# artPancreas.net
KiCad netlist of a schematic drawn in EAGLE
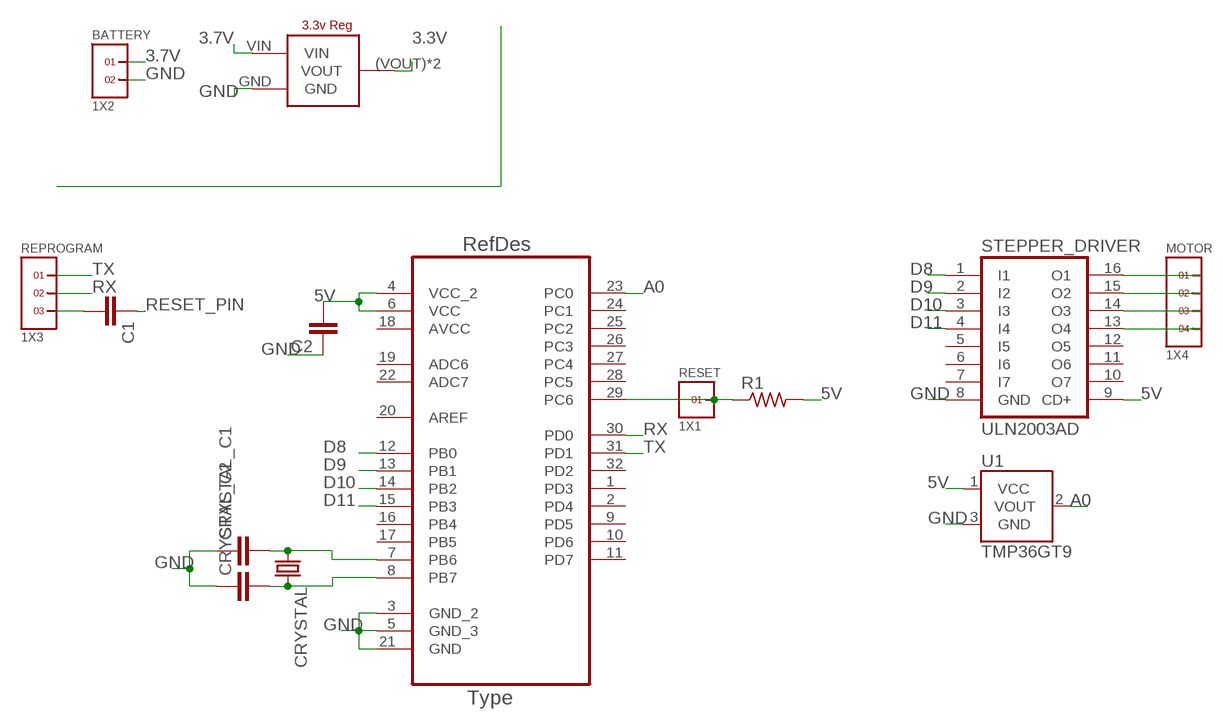
[diagram p0: schematic, sheet 1]

(export (version "E")
  (design (tool "Eeschema 10.0.6"))
  (components
    (comp (ref "ATMEGA328SMD")
      (value "ATMEGA328P-AU")
      (footprint "eagle-import:QFP80P900X900X120-32N")
      (libsource (lib "eagle-import") (part "ATMEGA328P-AU"))
    )
    (comp (ref "BATTERY")
      (value "1X2")
      (footprint "eagle-import:1X2")
      (libsource (lib "eagle-import") (part "1X2"))
    )
    (comp (ref "C1")
      (value "C2,5-3")
      (footprint "eagle-import:C2.5-3")
      (libsource (lib "eagle-import") (part "C2,5-3"))
    )
    (comp (ref "C2")
      (value "C2,5-3")
      (footprint "eagle-import:C2.5-3")
      (libsource (lib "eagle-import") (part "C2,5-3"))
    )
    (comp (ref "CRYSTAL")
      (value "CRYSTALHC18U-V")
      (footprint "eagle-import:HC18U-V")
      (libsource (lib "eagle-import") (part "CRYSTALHC18U-V"))
    )
    (comp (ref "CRYSTAL_C1")
      (value "C2,5-3")
      (footprint "eagle-import:C2.5-3")
      (libsource (lib "eagle-import") (part "C2,5-3"))
    )
    (comp (ref "CRYSTAL_C2")
      (value "C2,5-3")
      (footprint "eagle-import:C2.5-3")
      (libsource (lib "eagle-import") (part "C2,5-3"))
    )
    (comp (ref "MOTOR")
      (value "1X4")
      (footprint "eagle-import:1X4")
      (libsource (lib "eagle-import") (part "1X4"))
    )
    (comp (ref "R1")
      (value "R-US_0204/5")
      (footprint "eagle-import:0204_5")
      (libsource (lib "eagle-import") (part "R-US_0204/5"))
    )
    (comp (ref "REPROGRAM")
      (value "1X3")
      (footprint "eagle-import:1X3")
      (libsource (lib "eagle-import") (part "1X3"))
    )
    (comp (ref "RESET")
      (value "1X1")
      (footprint "eagle-import:1X1")
      (libsource (lib "eagle-import") (part "1X1"))
    )
    (comp (ref "STEPPER_DRIVER")
      (value "ULN2003AD")
      (footprint "eagle-import:SO16")
      (libsource (lib "eagle-import") (part "ULN2003AD"))
    )
    (comp (ref "U$1")
      (value "LD1117")
      (footprint "eagle-import:LD1117SOT-223")
      (libsource (lib "eagle-import") (part "LD1117"))
    )
    (comp (ref "U1")
      (value "TMP36GT9")
      (footprint "eagle-import:TO-92")
      (fields (field (name "MF") "Analog Devices") (field (name "MP") "TMP36"))
      (libsource (lib "eagle-import") (part "TMP36GT9"))
    )
  )
  (nets
    (net (code "1") (name "/3.3V") (class "Default")
      (node (ref "U$1") (pin "(VOUT)") (pinfunction "VOUT_(VOUT)") (pintype "bidirectional"))
      (node (ref "U$1") (pin "VOUT") (pinfunction "VOUT_VOUT") (pintype "bidirectional"))
    )
    (net (code "2") (name "/3.7V") (class "Default")
      (node (ref "BATTERY") (pin "1") (pinfunction "1_1") (pintype "bidirectional"))
      (node (ref "U$1") (pin "VIN") (pinfunction "VIN_VIN") (pintype "bidirectional"))
    )
    (net (code "3") (name "/5V") (class "Default")
      (node (ref "ATMEGA328SMD") (pin "4") (pinfunction "VCC_2_4") (pintype "power_in"))
      (node (ref "ATMEGA328SMD") (pin "6") (pinfunction "VCC_6") (pintype "power_in"))
      (node (ref "C2") (pin "2") (pinfunction "2_2") (pintype "passive"))
      (node (ref "R1") (pin "2") (pinfunction "2_2") (pintype "passive"))
      (node (ref "STEPPER_DRIVER") (pin "9") (pinfunction "CD+_9") (pintype "passive"))
      (node (ref "U1") (pin "1") (pinfunction "VCC_1") (pintype "bidirectional"))
    )
    (net (code "4") (name "/A0") (class "Default")
      (node (ref "ATMEGA328SMD") (pin "23") (pinfunction "PC0_23") (pintype "bidirectional"))
      (node (ref "U1") (pin "2") (pinfunction "VOUT_2") (pintype "bidirectional"))
    )
    (net (code "5") (name "/AVCC") (class "Default")
      (node (ref "ATMEGA328SMD") (pin "18") (pinfunction "AVCC_18") (pintype "power_in"))
    )
    (net (code "6") (name "/D8") (class "Default")
      (node (ref "ATMEGA328SMD") (pin "12") (pinfunction "PB0_12") (pintype "bidirectional"))
      (node (ref "STEPPER_DRIVER") (pin "1") (pinfunction "I1_1") (pintype "input"))
    )
    (net (code "7") (name "/D9") (class "Default")
      (node (ref "ATMEGA328SMD") (pin "13") (pinfunction "PB1_13") (pintype "bidirectional"))
      (node (ref "STEPPER_DRIVER") (pin "2") (pinfunction "I2_2") (pintype "input"))
    )
    (net (code "8") (name "/D10") (class "Default")
      (node (ref "ATMEGA328SMD") (pin "14") (pinfunction "PB2_14") (pintype "bidirectional"))
      (node (ref "STEPPER_DRIVER") (pin "3") (pinfunction "I3_3") (pintype "input"))
    )
    (net (code "9") (name "/D11") (class "Default")
      (node (ref "ATMEGA328SMD") (pin "15") (pinfunction "PB3_15") (pintype "bidirectional"))
      (node (ref "STEPPER_DRIVER") (pin "4") (pinfunction "I4_4") (pintype "input"))
    )
    (net (code "10") (name "/GND") (class "Default")
      (node (ref "ATMEGA328SMD") (pin "21") (pinfunction "GND_21") (pintype "passive"))
      (node (ref "ATMEGA328SMD") (pin "3") (pinfunction "GND_2_3") (pintype "passive"))
      (node (ref "ATMEGA328SMD") (pin "5") (pinfunction "GND_3_5") (pintype "passive"))
      (node (ref "BATTERY") (pin "2") (pinfunction "2_2") (pintype "bidirectional"))
      (node (ref "C2") (pin "1") (pinfunction "1_1") (pintype "passive"))
      (node (ref "CRYSTAL_C1") (pin "1") (pinfunction "1_1") (pintype "passive"))
      (node (ref "CRYSTAL_C2") (pin "1") (pinfunction "1_1") (pintype "passive"))
      (node (ref "STEPPER_DRIVER") (pin "8") (pinfunction "GND_8") (pintype "power_in"))
      (node (ref "U$1") (pin "GND") (pinfunction "GND_GND") (pintype "bidirectional"))
      (node (ref "U1") (pin "3") (pinfunction "GND_3") (pintype "bidirectional"))
    )
    (net (code "11") (name "/RESET_PIN") (class "Default")
      (node (ref "ATMEGA328SMD") (pin "29") (pinfunction "PC6_29") (pintype "bidirectional"))
      (node (ref "C1") (pin "1") (pinfunction "1_1") (pintype "passive"))
      (node (ref "R1") (pin "1") (pinfunction "1_1") (pintype "passive"))
      (node (ref "RESET") (pin "1") (pinfunction "1_1") (pintype "bidirectional"))
    )
    (net (code "12") (name "/RX") (class "Default")
      (node (ref "ATMEGA328SMD") (pin "30") (pinfunction "PD0_30") (pintype "bidirectional"))
      (node (ref "REPROGRAM") (pin "2") (pinfunction "2_2") (pintype "bidirectional"))
    )
    (net (code "13") (name "/TX") (class "Default")
      (node (ref "ATMEGA328SMD") (pin "31") (pinfunction "PD1_31") (pintype "bidirectional"))
      (node (ref "REPROGRAM") (pin "1") (pinfunction "1_1") (pintype "bidirectional"))
    )
    (net (code "14") (name "Net-(ATMEGA328SMD-PB6)") (class "Default")
      (node (ref "ATMEGA328SMD") (pin "7") (pinfunction "PB6_7") (pintype "bidirectional"))
      (node (ref "CRYSTAL") (pin "1") (pinfunction "1_1") (pintype "passive"))
      (node (ref "CRYSTAL_C1") (pin "2") (pinfunction "2_2") (pintype "passive"))
    )
    (net (code "15") (name "Net-(ATMEGA328SMD-PB7)") (class "Default")
      (node (ref "ATMEGA328SMD") (pin "8") (pinfunction "PB7_8") (pintype "bidirectional"))
      (node (ref "CRYSTAL") (pin "2") (pinfunction "2_2") (pintype "passive"))
      (node (ref "CRYSTAL_C2") (pin "2") (pinfunction "2_2") (pintype "passive"))
    )
    (net (code "16") (name "Net-(C1-Pad2)") (class "Default")
      (node (ref "C1") (pin "2") (pinfunction "2_2") (pintype "passive"))
      (node (ref "REPROGRAM") (pin "3") (pinfunction "3_3") (pintype "bidirectional"))
    )
    (net (code "17") (name "Net-(STEPPER_DRIVER-O1)") (class "Default")
      (node (ref "MOTOR") (pin "1") (pinfunction "1_1") (pintype "bidirectional"))
      (node (ref "STEPPER_DRIVER") (pin "16") (pinfunction "O1_16") (pintype "open_collector"))
    )
    (net (code "18") (name "Net-(STEPPER_DRIVER-O2)") (class "Default")
      (node (ref "MOTOR") (pin "2") (pinfunction "2_2") (pintype "bidirectional"))
      (node (ref "STEPPER_DRIVER") (pin "15") (pinfunction "O2_15") (pintype "open_collector"))
    )
    (net (code "19") (name "Net-(STEPPER_DRIVER-O3)") (class "Default")
      (node (ref "MOTOR") (pin "3") (pinfunction "3_3") (pintype "bidirectional"))
      (node (ref "STEPPER_DRIVER") (pin "14") (pinfunction "O3_14") (pintype "open_collector"))
    )
    (net (code "20") (name "Net-(STEPPER_DRIVER-O4)") (class "Default")
      (node (ref "MOTOR") (pin "4") (pinfunction "4_4") (pintype "bidirectional"))
      (node (ref "STEPPER_DRIVER") (pin "13") (pinfunction "O4_13") (pintype "open_collector"))
    )
    (net (code "21") (name "unconnected-(ATMEGA328SMD-ADC6-Pad19)") (class "Default")
      (node (ref "ATMEGA328SMD") (pin "19") (pinfunction "ADC6_19") (pintype "input"))
    )
    (net (code "22") (name "unconnected-(ATMEGA328SMD-ADC7-Pad22)") (class "Default")
      (node (ref "ATMEGA328SMD") (pin "22") (pinfunction "ADC7_22") (pintype "input"))
    )
    (net (code "23") (name "unconnected-(ATMEGA328SMD-AREF-Pad20)") (class "Default")
      (node (ref "ATMEGA328SMD") (pin "20") (pinfunction "AREF_20") (pintype "input"))
    )
    (net (code "24") (name "unconnected-(ATMEGA328SMD-PB4-Pad16)") (class "Default")
      (node (ref "ATMEGA328SMD") (pin "16") (pinfunction "PB4_16") (pintype "bidirectional"))
    )
    (net (code "25") (name "unconnected-(ATMEGA328SMD-PB5-Pad17)") (class "Default")
      (node (ref "ATMEGA328SMD") (pin "17") (pinfunction "PB5_17") (pintype "bidirectional"))
    )
    (net (code "26") (name "unconnected-(ATMEGA328SMD-PC1-Pad24)") (class "Default")
      (node (ref "ATMEGA328SMD") (pin "24") (pinfunction "PC1_24") (pintype "bidirectional"))
    )
    (net (code "27") (name "unconnected-(ATMEGA328SMD-PC2-Pad25)") (class "Default")
      (node (ref "ATMEGA328SMD") (pin "25") (pinfunction "PC2_25") (pintype "bidirectional"))
    )
    (net (code "28") (name "unconnected-(ATMEGA328SMD-PC3-Pad26)") (class "Default")
      (node (ref "ATMEGA328SMD") (pin "26") (pinfunction "PC3_26") (pintype "bidirectional"))
    )
    (net (code "29") (name "unconnected-(ATMEGA328SMD-PC4-Pad27)") (class "Default")
      (node (ref "ATMEGA328SMD") (pin "27") (pinfunction "PC4_27") (pintype "bidirectional"))
    )
    (net (code "30") (name "unconnected-(ATMEGA328SMD-PC5-Pad28)") (class "Default")
      (node (ref "ATMEGA328SMD") (pin "28") (pinfunction "PC5_28") (pintype "bidirectional"))
    )
    (net (code "31") (name "unconnected-(ATMEGA328SMD-PD2-Pad32)") (class "Default")
      (node (ref "ATMEGA328SMD") (pin "32") (pinfunction "PD2_32") (pintype "bidirectional"))
    )
    (net (code "32") (name "unconnected-(ATMEGA328SMD-PD3-Pad1)") (class "Default")
      (node (ref "ATMEGA328SMD") (pin "1") (pinfunction "PD3_1") (pintype "bidirectional"))
    )
    (net (code "33") (name "unconnected-(ATMEGA328SMD-PD4-Pad2)") (class "Default")
      (node (ref "ATMEGA328SMD") (pin "2") (pinfunction "PD4_2") (pintype "bidirectional"))
    )
    (net (code "34") (name "unconnected-(ATMEGA328SMD-PD5-Pad9)") (class "Default")
      (node (ref "ATMEGA328SMD") (pin "9") (pinfunction "PD5_9") (pintype "bidirectional"))
    )
    (net (code "35") (name "unconnected-(ATMEGA328SMD-PD6-Pad10)") (class "Default")
      (node (ref "ATMEGA328SMD") (pin "10") (pinfunction "PD6_10") (pintype "bidirectional"))
    )
    (net (code "36") (name "unconnected-(ATMEGA328SMD-PD7-Pad11)") (class "Default")
      (node (ref "ATMEGA328SMD") (pin "11") (pinfunction "PD7_11") (pintype "bidirectional"))
    )
    (net (code "37") (name "unconnected-(STEPPER_DRIVER-I5-Pad5)") (class "Default")
      (node (ref "STEPPER_DRIVER") (pin "5") (pinfunction "I5_5") (pintype "input"))
    )
    (net (code "38") (name "unconnected-(STEPPER_DRIVER-I6-Pad6)") (class "Default")
      (node (ref "STEPPER_DRIVER") (pin "6") (pinfunction "I6_6") (pintype "input"))
    )
    (net (code "39") (name "unconnected-(STEPPER_DRIVER-I7-Pad7)") (class "Default")
      (node (ref "STEPPER_DRIVER") (pin "7") (pinfunction "I7_7") (pintype "input"))
    )
    (net (code "40") (name "unconnected-(STEPPER_DRIVER-O5-Pad12)") (class "Default")
      (node (ref "STEPPER_DRIVER") (pin "12") (pinfunction "O5_12") (pintype "open_collector"))
    )
    (net (code "41") (name "unconnected-(STEPPER_DRIVER-O6-Pad11)") (class "Default")
      (node (ref "STEPPER_DRIVER") (pin "11") (pinfunction "O6_11") (pintype "open_collector"))
    )
    (net (code "42") (name "unconnected-(STEPPER_DRIVER-O7-Pad10)") (class "Default")
      (node (ref "STEPPER_DRIVER") (pin "10") (pinfunction "O7_10") (pintype "open_collector"))
    )
  )
)
